# POWER.net
KiCad netlist of a schematic drawn in Altium Designer
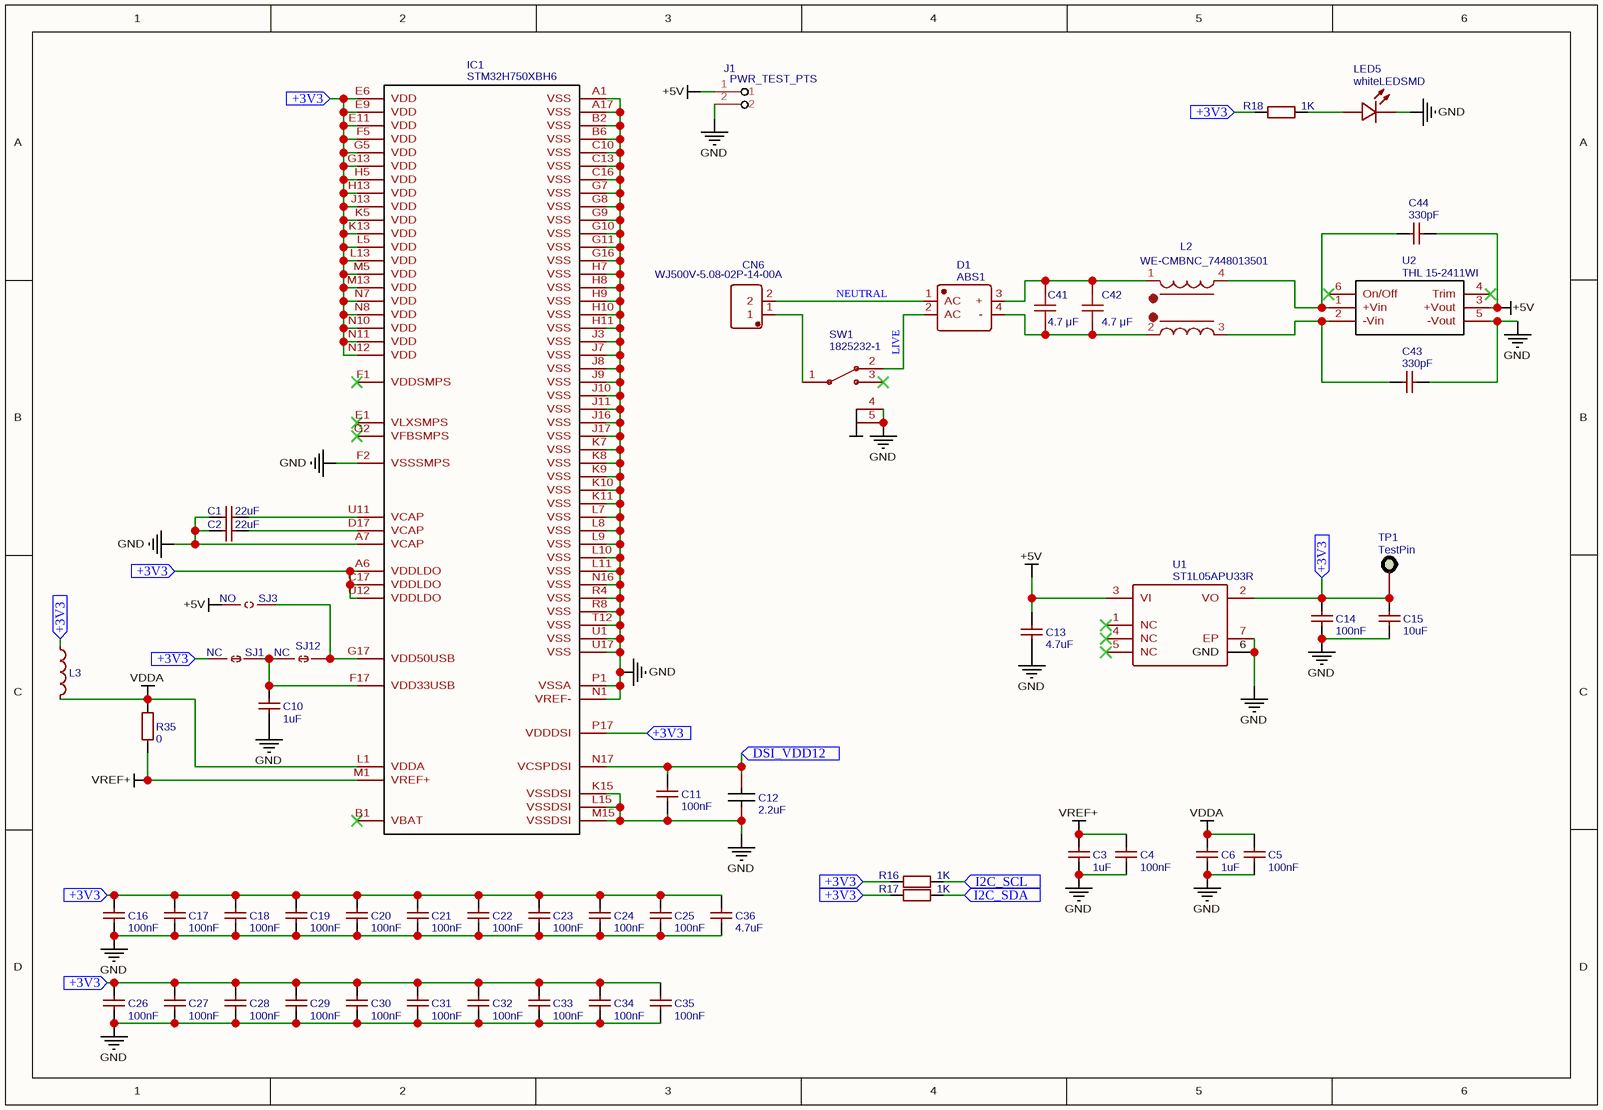
[diagram p0: POWER.schdoc]

(export (version "E")
  (design (tool "Eeschema 10.0.6"))
  (components
    (comp (ref "C1")
      (value "22uF")
      (fields
        (field (name "BOM_MANUFACTURER PART") "CL31A226KPHNNNE")
        (field (name "BOM_SUPPLIER PART") "C5672")
      )
      (libsource (lib "altium-import") (part "root_0_22uF_"))
    )
    (comp (ref "C2")
      (value "22uF")
      (fields
        (field (name "BOM_MANUFACTURER PART") "CL31A226KPHNNNE")
        (field (name "BOM_SUPPLIER PART") "C5672")
      )
      (libsource (lib "altium-import") (part "root_0_22uF_"))
    )
    (comp (ref "C3")
      (value "1uF")
      (fields
        (field (name "BOM_MANUFACTURER PART") "CL10A105KB8NNNC")
        (field (name "BOM_SUPPLIER PART") "C15849")
      )
      (libsource (lib "altium-import") (part "root_1_1uF_"))
    )
    (comp (ref "C4")
      (value "100nF")
      (fields
        (field (name "BOM_MANUFACTURER PART") "CL05B104KO5NNNC")
        (field (name "BOM_SUPPLIER PART") "C1525")
      )
      (libsource (lib "altium-import") (part "root_1_100nF_"))
    )
    (comp (ref "C5")
      (value "100nF")
      (fields
        (field (name "BOM_MANUFACTURER PART") "CL05B104KO5NNNC")
        (field (name "BOM_SUPPLIER PART") "C1525")
      )
      (libsource (lib "altium-import") (part "root_1_100nF_"))
    )
    (comp (ref "C6")
      (value "1uF")
      (fields
        (field (name "BOM_MANUFACTURER PART") "CL10A105KB8NNNC")
        (field (name "BOM_SUPPLIER PART") "C15849")
      )
      (libsource (lib "altium-import") (part "root_1_1uF_"))
    )
    (comp (ref "C10")
      (value "1uF")
      (fields
        (field (name "BOM_MANUFACTURER PART") "CL10A105KB8NNNC")
        (field (name "BOM_SUPPLIER PART") "C15849")
      )
      (libsource (lib "altium-import") (part "root_1_1uF_"))
    )
    (comp (ref "C11")
      (value "100nF")
      (fields
        (field (name "BOM_MANUFACTURER PART") "CL05B104KO5NNNC")
        (field (name "BOM_SUPPLIER PART") "C1525")
      )
      (libsource (lib "altium-import") (part "root_1_100nF_"))
    )
    (comp (ref "C12")
      (value "2.2uF")
      (fields
        (field (name "BOM_MANUFACTURER PART") "CL05A225MQ5NSNC")
        (field (name "BOM_SUPPLIER PART") "C12530")
      )
      (libsource (lib "altium-import") (part "root_1_2.2uF_"))
    )
    (comp (ref "C13")
      (value "4.7uF")
      (fields
        (field (name "BOM_MANUFACTURER PART") "CL05A475MP5NRNC")
        (field (name "BOM_SUPPLIER PART") "C23733")
      )
      (libsource (lib "altium-import") (part "root_1_4.7uF_"))
    )
    (comp (ref "C14")
      (value "100nF")
      (fields
        (field (name "BOM_MANUFACTURER PART") "CL05B104KO5NNNC")
        (field (name "BOM_SUPPLIER PART") "C1525")
      )
      (libsource (lib "altium-import") (part "root_1_100nF_"))
    )
    (comp (ref "C15")
      (value "10uF")
      (fields
        (field (name "BOM_MANUFACTURER PART") "CL21A106KAYNNNE")
        (field (name "BOM_SUPPLIER PART") "C15850")
      )
      (libsource (lib "altium-import") (part "root_1_10uF_"))
    )
    (comp (ref "C16")
      (value "100nF")
      (fields
        (field (name "BOM_MANUFACTURER PART") "CL05B104KO5NNNC")
        (field (name "BOM_SUPPLIER PART") "C1525")
      )
      (libsource (lib "altium-import") (part "root_1_100nF_"))
    )
    (comp (ref "C17")
      (value "100nF")
      (fields
        (field (name "BOM_MANUFACTURER PART") "CL05B104KO5NNNC")
        (field (name "BOM_SUPPLIER PART") "C1525")
      )
      (libsource (lib "altium-import") (part "root_1_100nF_"))
    )
    (comp (ref "C18")
      (value "100nF")
      (fields
        (field (name "BOM_MANUFACTURER PART") "CL05B104KO5NNNC")
        (field (name "BOM_SUPPLIER PART") "C1525")
      )
      (libsource (lib "altium-import") (part "root_1_100nF_"))
    )
    (comp (ref "C19")
      (value "100nF")
      (fields
        (field (name "BOM_MANUFACTURER PART") "CL05B104KO5NNNC")
        (field (name "BOM_SUPPLIER PART") "C1525")
      )
      (libsource (lib "altium-import") (part "root_1_100nF_"))
    )
    (comp (ref "C20")
      (value "100nF")
      (fields
        (field (name "BOM_MANUFACTURER PART") "CL05B104KO5NNNC")
        (field (name "BOM_SUPPLIER PART") "C1525")
      )
      (libsource (lib "altium-import") (part "root_1_100nF_"))
    )
    (comp (ref "C21")
      (value "100nF")
      (fields
        (field (name "BOM_MANUFACTURER PART") "CL05B104KO5NNNC")
        (field (name "BOM_SUPPLIER PART") "C1525")
      )
      (libsource (lib "altium-import") (part "root_1_100nF_"))
    )
    (comp (ref "C22")
      (value "100nF")
      (fields
        (field (name "BOM_MANUFACTURER PART") "CL05B104KO5NNNC")
        (field (name "BOM_SUPPLIER PART") "C1525")
      )
      (libsource (lib "altium-import") (part "root_1_100nF_"))
    )
    (comp (ref "C23")
      (value "100nF")
      (fields
        (field (name "BOM_MANUFACTURER PART") "CL05B104KO5NNNC")
        (field (name "BOM_SUPPLIER PART") "C1525")
      )
      (libsource (lib "altium-import") (part "root_1_100nF_"))
    )
    (comp (ref "C24")
      (value "100nF")
      (fields
        (field (name "BOM_MANUFACTURER PART") "CL05B104KO5NNNC")
        (field (name "BOM_SUPPLIER PART") "C1525")
      )
      (libsource (lib "altium-import") (part "root_1_100nF_"))
    )
    (comp (ref "C25")
      (value "100nF")
      (fields
        (field (name "BOM_MANUFACTURER PART") "CL05B104KO5NNNC")
        (field (name "BOM_SUPPLIER PART") "C1525")
      )
      (libsource (lib "altium-import") (part "root_1_100nF_"))
    )
    (comp (ref "C26")
      (value "100nF")
      (fields
        (field (name "BOM_MANUFACTURER PART") "CL05B104KO5NNNC")
        (field (name "BOM_SUPPLIER PART") "C1525")
      )
      (libsource (lib "altium-import") (part "root_1_100nF_"))
    )
    (comp (ref "C27")
      (value "100nF")
      (fields
        (field (name "BOM_MANUFACTURER PART") "CL05B104KO5NNNC")
        (field (name "BOM_SUPPLIER PART") "C1525")
      )
      (libsource (lib "altium-import") (part "root_1_100nF_"))
    )
    (comp (ref "C28")
      (value "100nF")
      (fields
        (field (name "BOM_MANUFACTURER PART") "CL05B104KO5NNNC")
        (field (name "BOM_SUPPLIER PART") "C1525")
      )
      (libsource (lib "altium-import") (part "root_1_100nF_"))
    )
    (comp (ref "C29")
      (value "100nF")
      (fields
        (field (name "BOM_MANUFACTURER PART") "CL05B104KO5NNNC")
        (field (name "BOM_SUPPLIER PART") "C1525")
      )
      (libsource (lib "altium-import") (part "root_1_100nF_"))
    )
    (comp (ref "C30")
      (value "100nF")
      (fields
        (field (name "BOM_MANUFACTURER PART") "CL05B104KO5NNNC")
        (field (name "BOM_SUPPLIER PART") "C1525")
      )
      (libsource (lib "altium-import") (part "root_1_100nF_"))
    )
    (comp (ref "C31")
      (value "100nF")
      (fields
        (field (name "BOM_MANUFACTURER PART") "CL05B104KO5NNNC")
        (field (name "BOM_SUPPLIER PART") "C1525")
      )
      (libsource (lib "altium-import") (part "root_1_100nF_"))
    )
    (comp (ref "C32")
      (value "100nF")
      (fields
        (field (name "BOM_MANUFACTURER PART") "CL05B104KO5NNNC")
        (field (name "BOM_SUPPLIER PART") "C1525")
      )
      (libsource (lib "altium-import") (part "root_1_100nF_"))
    )
    (comp (ref "C33")
      (value "100nF")
      (fields
        (field (name "BOM_MANUFACTURER PART") "CL05B104KO5NNNC")
        (field (name "BOM_SUPPLIER PART") "C1525")
      )
      (libsource (lib "altium-import") (part "root_1_100nF_"))
    )
    (comp (ref "C34")
      (value "100nF")
      (fields
        (field (name "BOM_MANUFACTURER PART") "CL05B104KO5NNNC")
        (field (name "BOM_SUPPLIER PART") "C1525")
      )
      (libsource (lib "altium-import") (part "root_1_100nF_"))
    )
    (comp (ref "C35")
      (value "100nF")
      (fields
        (field (name "BOM_MANUFACTURER PART") "CL05B104KO5NNNC")
        (field (name "BOM_SUPPLIER PART") "C1525")
      )
      (libsource (lib "altium-import") (part "root_1_100nF_"))
    )
    (comp (ref "C36")
      (value "4.7uF")
      (fields
        (field (name "BOM_MANUFACTURER PART") "CL05A475MP5NRNC")
        (field (name "BOM_SUPPLIER PART") "C23733")
      )
      (libsource (lib "altium-import") (part "root_1_4.7uF_"))
    )
    (comp (ref "C41")
      (value "4.7 μF")
      (fields (field (name "BOM_SUPPLIER PART") "C16036") (field (name "CONTRIBUTOR") "LCSC"))
      (libsource (lib "altium-import") (part "root_0_4.7 μF_"))
    )
    (comp (ref "C42")
      (value "4.7 μF")
      (fields (field (name "BOM_SUPPLIER PART") "C16036") (field (name "CONTRIBUTOR") "LCSC"))
      (libsource (lib "altium-import") (part "root_0_4.7 μF_"))
    )
    (comp (ref "C43")
      (value "330pF")
      (fields
        (field (name "BOM_MANUFACTURER PART") "1206B331K501NT")
        (field (name "BOM_SUPPLIER PART") "C46377")
      )
      (libsource (lib "altium-import") (part "root_0_330pF_"))
    )
    (comp (ref "C44")
      (value "330pF")
      (fields
        (field (name "BOM_MANUFACTURER PART") "1206B331K501NT")
        (field (name "BOM_SUPPLIER PART") "C46377")
      )
      (libsource (lib "altium-import") (part "root_0_330pF_"))
    )
    (comp (ref "CN6")
      (value "WJ500V-5.08-02P-14-00A")
      (fields (field (name "BOM_SUPPLIER PART") "C138464") (field (name "CONTRIBUTOR") "LCSC"))
      (libsource (lib "altium-import") (part "root_2_WJ500V-5.08-02P-14-00A_"))
    )
    (comp (ref "D1")
      (value "ABS1")
      (fields (field (name "BOM_SUPPLIER PART") "C130890") (field (name "CONTRIBUTOR") "LCSC"))
      (libsource (lib "altium-import") (part "root_0_ABS1_"))
    )
    (comp (ref "IC1")
      (value "STM32H750XBH6")
      (fields (field (name "SUBPART_NO") "1") (field (name "CONTRIBUTOR") "Ke'Ondrae_Mell"))
      (libsource (lib "altium-import") (part "root_0_STM32H750XBH6_"))
    )
    (comp (ref "J1")
      (value "PWR_TEST_PTS")
      (fields (field (name "CONTRIBUTOR") "Claudio Quartarone"))
      (libsource (lib "altium-import") (part "root_3_PWR_TEST_PTS_"))
    )
    (comp (ref "L2")
      (value "WE-CMBNC_7448013501")
      (description "WE-CMBNC Common Mode Power Line Choke Nanocrystalline")
      (libsource (lib "altium-import") (part "root_0_WE-CMBNC_7448013501_"))
    )
    (comp (ref "L3")
      (value "FCM1608KF-601T03")
      (fields (field (name "BOM_SUPPLIER PART") "C141723") (field (name "CONTRIBUTOR") "LCSC"))
      (libsource (lib "altium-import") (part "root_3_FCM1608KF-601T03_"))
    )
    (comp (ref "LED5")
      (value "whiteLEDSMD")
      (fields (field (name "BOM_SUPPLIER PART") "C34499"))
      (libsource (lib "altium-import") (part "root_0_whiteLEDSMD_"))
    )
    (comp (ref "R16")
      (value "1K")
      (fields
        (field (name "BOM_MANUFACTURER PART") "0402WGF1001TCE")
        (field (name "BOM_SUPPLIER PART") "C11702")
      )
      (libsource (lib "altium-import") (part "root_0_1K_"))
    )
    (comp (ref "R17")
      (value "1K")
      (fields
        (field (name "BOM_MANUFACTURER PART") "0402WGF1001TCE")
        (field (name "BOM_SUPPLIER PART") "C11702")
      )
      (libsource (lib "altium-import") (part "root_0_1K_"))
    )
    (comp (ref "R18")
      (value "1K")
      (fields
        (field (name "BOM_MANUFACTURER PART") "0402WGF1001TCE")
        (field (name "BOM_SUPPLIER PART") "C11702")
      )
      (libsource (lib "altium-import") (part "root_0_1K_"))
    )
    (comp (ref "R35")
      (value "0")
      (fields
        (field (name "BOM_MANUFACTURER PART") "RK73Z1ETTP")
        (field (name "BOM_SUPPLIER PART") "C131359")
      )
      (libsource (lib "altium-import") (part "root_1_0_"))
    )
    (comp (ref "SJ1")
      (value "NC")
      (fields (field (name "CONTRIBUTOR") "SparkFun"))
      (libsource (lib "altium-import") (part "root_0_NC_"))
    )
    (comp (ref "SJ3")
      (value "NO")
      (fields (field (name "CONTRIBUTOR") "SparkFun"))
      (libsource (lib "altium-import") (part "root_0_NO_"))
    )
    (comp (ref "SJ12")
      (value "NC")
      (fields (field (name "CONTRIBUTOR") "SparkFun"))
      (libsource (lib "altium-import") (part "root_0_NC_"))
    )
    (comp (ref "SW1")
      (value "1825232-1")
      (fields (field (name "BOM_SUPPLIER PART") "655-1825232-1") (field (name "CONTRIBUTOR") "nathantct"))
      (libsource (lib "altium-import") (part "root_0_1825232-1_"))
    )
    (comp (ref "TP1")
      (value "TestPin")
      (fields (field (name "CONTRIBUTOR") "alan.green"))
      (libsource (lib "altium-import") (part "root_0_TestPin_"))
    )
    (comp (ref "U1")
      (value "ST1L05APU33R")
      (description "Very Low Quiescent BiCMOS Voltage Regulator, 3.3V, 6-Pin VFDFPN, Tape and Reel")
      (libsource (lib "altium-import") (part "root_0_ST1L05APU33R_"))
    )
    (comp (ref "U2")
      (value "THL 15-2411WI")
      (fields
        (field (name "BOM_SUPPLIER PART") "1951-3321-ND")
        (field (name "CONTRIBUTOR") "louis.grueninger")
      )
      (libsource (lib "altium-import") (part "root_0_THL 15-2411WI_"))
    )
  )
  (nets
    (net (code "1") (name "+5V") (class "Default")
      (node (ref "C13") (pin "2") (pinfunction "2_2") (pintype "passive"))
      (node (ref "C44") (pin "2") (pinfunction "2_2") (pintype "passive"))
      (node (ref "J1") (pin "1") (pinfunction "1_1") (pintype "passive"))
      (node (ref "SJ3") (pin "1") (pinfunction "1_1") (pintype "passive"))
      (node (ref "U1") (pin "3") (pinfunction "VI_3") (pintype "passive"))
      (node (ref "U2") (pin "3") (pinfunction "+Vout_3") (pintype "passive"))
    )
    (net (code "2") (name "/+3V3") (class "Default")
      (node (ref "C14") (pin "2") (pinfunction "2_2") (pintype "passive"))
      (node (ref "C15") (pin "2") (pinfunction "2_2") (pintype "passive"))
      (node (ref "C16") (pin "2") (pinfunction "2_2") (pintype "passive"))
      (node (ref "C17") (pin "2") (pinfunction "2_2") (pintype "passive"))
      (node (ref "C18") (pin "2") (pinfunction "2_2") (pintype "passive"))
      (node (ref "C19") (pin "2") (pinfunction "2_2") (pintype "passive"))
      (node (ref "C20") (pin "2") (pinfunction "2_2") (pintype "passive"))
      (node (ref "C21") (pin "2") (pinfunction "2_2") (pintype "passive"))
      (node (ref "C22") (pin "2") (pinfunction "2_2") (pintype "passive"))
      (node (ref "C23") (pin "2") (pinfunction "2_2") (pintype "passive"))
      (node (ref "C24") (pin "2") (pinfunction "2_2") (pintype "passive"))
      (node (ref "C25") (pin "2") (pinfunction "2_2") (pintype "passive"))
      (node (ref "C26") (pin "2") (pinfunction "2_2") (pintype "passive"))
      (node (ref "C27") (pin "2") (pinfunction "2_2") (pintype "passive"))
      (node (ref "C28") (pin "2") (pinfunction "2_2") (pintype "passive"))
      (node (ref "C29") (pin "2") (pinfunction "2_2") (pintype "passive"))
      (node (ref "C30") (pin "2") (pinfunction "2_2") (pintype "passive"))
      (node (ref "C31") (pin "2") (pinfunction "2_2") (pintype "passive"))
      (node (ref "C32") (pin "2") (pinfunction "2_2") (pintype "passive"))
      (node (ref "C33") (pin "2") (pinfunction "2_2") (pintype "passive"))
      (node (ref "C34") (pin "2") (pinfunction "2_2") (pintype "passive"))
      (node (ref "C35") (pin "2") (pinfunction "2_2") (pintype "passive"))
      (node (ref "C36") (pin "2") (pinfunction "2_2") (pintype "passive"))
      (node (ref "IC1") (pin "A6") (pinfunction "VDDLDO_A6") (pintype "passive"))
      (node (ref "IC1") (pin "C17") (pinfunction "VDDLDO_C17") (pintype "passive"))
      (node (ref "IC1") (pin "E11") (pinfunction "VDD_E11") (pintype "passive"))
      (node (ref "IC1") (pin "E6") (pinfunction "VDD_E6") (pintype "passive"))
      (node (ref "IC1") (pin "E9") (pinfunction "VDD_E9") (pintype "passive"))
      (node (ref "IC1") (pin "F5") (pinfunction "VDD_F5") (pintype "passive"))
      (node (ref "IC1") (pin "G13") (pinfunction "VDD_G13") (pintype "passive"))
      (node (ref "IC1") (pin "G5") (pinfunction "VDD_G5") (pintype "passive"))
      (node (ref "IC1") (pin "H13") (pinfunction "VDD_H13") (pintype "passive"))
      (node (ref "IC1") (pin "H5") (pinfunction "VDD_H5") (pintype "passive"))
      (node (ref "IC1") (pin "J13") (pinfunction "VDD_J13") (pintype "passive"))
      (node (ref "IC1") (pin "K13") (pinfunction "VDD_K13") (pintype "passive"))
      (node (ref "IC1") (pin "K5") (pinfunction "VDD_K5") (pintype "passive"))
      (node (ref "IC1") (pin "L13") (pinfunction "VDD_L13") (pintype "passive"))
      (node (ref "IC1") (pin "L5") (pinfunction "VDD_L5") (pintype "passive"))
      (node (ref "IC1") (pin "M13") (pinfunction "VDD_M13") (pintype "passive"))
      (node (ref "IC1") (pin "M5") (pinfunction "VDD_M5") (pintype "passive"))
      (node (ref "IC1") (pin "N10") (pinfunction "VDD_N10") (pintype "passive"))
      (node (ref "IC1") (pin "N11") (pinfunction "VDD_N11") (pintype "passive"))
      (node (ref "IC1") (pin "N12") (pinfunction "VDD_N12") (pintype "passive"))
      (node (ref "IC1") (pin "N7") (pinfunction "VDD_N7") (pintype "passive"))
      (node (ref "IC1") (pin "N8") (pinfunction "VDD_N8") (pintype "passive"))
      (node (ref "IC1") (pin "P17") (pinfunction "VDDDSI_P17") (pintype "passive"))
      (node (ref "IC1") (pin "U12") (pinfunction "VDDLDO_U12") (pintype "passive"))
      (node (ref "L3") (pin "1") (pinfunction "1_1") (pintype "passive"))
      (node (ref "R16") (pin "1") (pinfunction "1_1") (pintype "passive"))
      (node (ref "R17") (pin "1") (pinfunction "1_1") (pintype "passive"))
      (node (ref "R18") (pin "1") (pinfunction "1_1") (pintype "passive"))
      (node (ref "SJ1") (pin "1") (pinfunction "1_1") (pintype "passive"))
      (node (ref "TP1") (pin "1") (pinfunction "1_1") (pintype "passive"))
      (node (ref "U1") (pin "2") (pinfunction "VO_2") (pintype "passive"))
    )
    (net (code "3") (name "/DSI_VDD12") (class "Default")
      (node (ref "C11") (pin "2") (pinfunction "2_2") (pintype "passive"))
      (node (ref "C12") (pin "2") (pinfunction "2_2") (pintype "passive"))
      (node (ref "IC1") (pin "N17") (pinfunction "VCSPDSI_N17") (pintype "passive"))
    )
    (net (code "4") (name "/I2C_SCL") (class "Default")
      (node (ref "R16") (pin "2") (pinfunction "2_2") (pintype "passive"))
    )
    (net (code "5") (name "/I2C_SDA") (class "Default")
      (node (ref "R17") (pin "2") (pinfunction "2_2") (pintype "passive"))
    )
    (net (code "6") (name "/LIVE") (class "Default")
      (node (ref "D1") (pin "2") (pinfunction "AC_2") (pintype "passive"))
      (node (ref "SW1") (pin "2") (pinfunction "2_2") (pintype "passive"))
    )
    (net (code "7") (name "/NEUTRAL") (class "Default")
      (node (ref "CN6") (pin "2") (pinfunction "2_2") (pintype "passive"))
      (node (ref "D1") (pin "1") (pinfunction "AC_1") (pintype "passive"))
    )
    (net (code "8") (name "GND") (class "Default")
      (node (ref "C1") (pin "1") (pinfunction "1_1") (pintype "passive"))
      (node (ref "C10") (pin "1") (pinfunction "1_1") (pintype "passive"))
      (node (ref "C11") (pin "1") (pinfunction "1_1") (pintype "passive"))
      (node (ref "C12") (pin "1") (pinfunction "1_1") (pintype "passive"))
      (node (ref "C13") (pin "1") (pinfunction "1_1") (pintype "passive"))
      (node (ref "C14") (pin "1") (pinfunction "1_1") (pintype "passive"))
      (node (ref "C15") (pin "1") (pinfunction "1_1") (pintype "passive"))
      (node (ref "C16") (pin "1") (pinfunction "1_1") (pintype "passive"))
      (node (ref "C17") (pin "1") (pinfunction "1_1") (pintype "passive"))
      (node (ref "C18") (pin "1") (pinfunction "1_1") (pintype "passive"))
      (node (ref "C19") (pin "1") (pinfunction "1_1") (pintype "passive"))
      (node (ref "C2") (pin "1") (pinfunction "1_1") (pintype "passive"))
      (node (ref "C20") (pin "1") (pinfunction "1_1") (pintype "passive"))
      (node (ref "C21") (pin "1") (pinfunction "1_1") (pintype "passive"))
      (node (ref "C22") (pin "1") (pinfunction "1_1") (pintype "passive"))
      (node (ref "C23") (pin "1") (pinfunction "1_1") (pintype "passive"))
      (node (ref "C24") (pin "1") (pinfunction "1_1") (pintype "passive"))
      (node (ref "C25") (pin "1") (pinfunction "1_1") (pintype "passive"))
      (node (ref "C26") (pin "1") (pinfunction "1_1") (pintype "passive"))
      (node (ref "C27") (pin "1") (pinfunction "1_1") (pintype "passive"))
      (node (ref "C28") (pin "1") (pinfunction "1_1") (pintype "passive"))
      (node (ref "C29") (pin "1") (pinfunction "1_1") (pintype "passive"))
      (node (ref "C3") (pin "1") (pinfunction "1_1") (pintype "passive"))
      (node (ref "C30") (pin "1") (pinfunction "1_1") (pintype "passive"))
      (node (ref "C31") (pin "1") (pinfunction "1_1") (pintype "passive"))
      (node (ref "C32") (pin "1") (pinfunction "1_1") (pintype "passive"))
      (node (ref "C33") (pin "1") (pinfunction "1_1") (pintype "passive"))
      (node (ref "C34") (pin "1") (pinfunction "1_1") (pintype "passive"))
      (node (ref "C35") (pin "1") (pinfunction "1_1") (pintype "passive"))
      (node (ref "C36") (pin "1") (pinfunction "1_1") (pintype "passive"))
      (node (ref "C4") (pin "1") (pinfunction "1_1") (pintype "passive"))
      (node (ref "C43") (pin "2") (pinfunction "2_2") (pintype "passive"))
      (node (ref "C5") (pin "1") (pinfunction "1_1") (pintype "passive"))
      (node (ref "C6") (pin "1") (pinfunction "1_1") (pintype "passive"))
      (node (ref "IC1") (pin "A1") (pinfunction "VSS_A1") (pintype "passive"))
      (node (ref "IC1") (pin "A17") (pinfunction "VSS_A17") (pintype "passive"))
      (node (ref "IC1") (pin "A7") (pinfunction "VCAP_A7") (pintype "passive"))
      (node (ref "IC1") (pin "B2") (pinfunction "VSS_B2") (pintype "passive"))
      (node (ref "IC1") (pin "B6") (pinfunction "VSS_B6") (pintype "passive"))
      (node (ref "IC1") (pin "C10") (pinfunction "VSS_C10") (pintype "passive"))
      (node (ref "IC1") (pin "C13") (pinfunction "VSS_C13") (pintype "passive"))
      (node (ref "IC1") (pin "C16") (pinfunction "VSS_C16") (pintype "passive"))
      (node (ref "IC1") (pin "F2") (pinfunction "VSSSMPS_F2") (pintype "passive"))
      (node (ref "IC1") (pin "G10") (pinfunction "VSS_G10") (pintype "passive"))
      (node (ref "IC1") (pin "G11") (pinfunction "VSS_G11") (pintype "passive"))
      (node (ref "IC1") (pin "G16") (pinfunction "VSS_G16") (pintype "passive"))
      (node (ref "IC1") (pin "G7") (pinfunction "VSS_G7") (pintype "passive"))
      (node (ref "IC1") (pin "G8") (pinfunction "VSS_G8") (pintype "passive"))
      (node (ref "IC1") (pin "G9") (pinfunction "VSS_G9") (pintype "passive"))
      (node (ref "IC1") (pin "H10") (pinfunction "VSS_H10") (pintype "passive"))
      (node (ref "IC1") (pin "H11") (pinfunction "VSS_H11") (pintype "passive"))
      (node (ref "IC1") (pin "H7") (pinfunction "VSS_H7") (pintype "passive"))
      (node (ref "IC1") (pin "H8") (pinfunction "VSS_H8") (pintype "passive"))
      (node (ref "IC1") (pin "H9") (pinfunction "VSS_H9") (pintype "passive"))
      (node (ref "IC1") (pin "J10") (pinfunction "VSS_J10") (pintype "passive"))
      (node (ref "IC1") (pin "J11") (pinfunction "VSS_J11") (pintype "passive"))
      (node (ref "IC1") (pin "J16") (pinfunction "VSS_J16") (pintype "passive"))
      (node (ref "IC1") (pin "J17") (pinfunction "VSS_J17") (pintype "passive"))
      (node (ref "IC1") (pin "J3") (pinfunction "VSS_J3") (pintype "passive"))
      (node (ref "IC1") (pin "J7") (pinfunction "VSS_J7") (pintype "passive"))
      (node (ref "IC1") (pin "J8") (pinfunction "VSS_J8") (pintype "passive"))
      (node (ref "IC1") (pin "J9") (pinfunction "VSS_J9") (pintype "passive"))
      (node (ref "IC1") (pin "K10") (pinfunction "VSS_K10") (pintype "passive"))
      (node (ref "IC1") (pin "K11") (pinfunction "VSS_K11") (pintype "passive"))
      (node (ref "IC1") (pin "K15") (pinfunction "VSSDSI_K15") (pintype "passive"))
      (node (ref "IC1") (pin "K7") (pinfunction "VSS_K7") (pintype "passive"))
      (node (ref "IC1") (pin "K8") (pinfunction "VSS_K8") (pintype "passive"))
      (node (ref "IC1") (pin "K9") (pinfunction "VSS_K9") (pintype "passive"))
      (node (ref "IC1") (pin "L10") (pinfunction "VSS_L10") (pintype "passive"))
      (node (ref "IC1") (pin "L11") (pinfunction "VSS_L11") (pintype "passive"))
      (node (ref "IC1") (pin "L15") (pinfunction "VSSDSI_L15") (pintype "passive"))
      (node (ref "IC1") (pin "L7") (pinfunction "VSS_L7") (pintype "passive"))
      (node (ref "IC1") (pin "L8") (pinfunction "VSS_L8") (pintype "passive"))
      (node (ref "IC1") (pin "L9") (pinfunction "VSS_L9") (pintype "passive"))
      (node (ref "IC1") (pin "M15") (pinfunction "VSSDSI_M15") (pintype "passive"))
      (node (ref "IC1") (pin "N1") (pinfunction "VREF-_N1") (pintype "passive"))
      (node (ref "IC1") (pin "N16") (pinfunction "VSS_N16") (pintype "passive"))
      (node (ref "IC1") (pin "P1") (pinfunction "VSSA_P1") (pintype "passive"))
      (node (ref "IC1") (pin "R4") (pinfunction "VSS_R4") (pintype "passive"))
      (node (ref "IC1") (pin "R8") (pinfunction "VSS_R8") (pintype "passive"))
      (node (ref "IC1") (pin "T12") (pinfunction "VSS_T12") (pintype "passive"))
      (node (ref "IC1") (pin "U1") (pinfunction "VSS_U1") (pintype "passive"))
      (node (ref "IC1") (pin "U17") (pinfunction "VSS_U17") (pintype "passive"))
      (node (ref "J1") (pin "2") (pinfunction "2_2") (pintype "passive"))
      (node (ref "LED5") (pin "2") (pinfunction "K_2") (pintype "passive"))
      (node (ref "SW1") (pin "4") (pinfunction "4_4") (pintype "passive"))
      (node (ref "SW1") (pin "5") (pinfunction "5_5") (pintype "passive"))
      (node (ref "U1") (pin "6") (pinfunction "GND_6") (pintype "passive"))
      (node (ref "U1") (pin "7") (pinfunction "EP_7") (pintype "passive"))
      (node (ref "U2") (pin "5") (pinfunction "-Vout_5") (pintype "passive"))
    )
    (net (code "9") (name "Net-(C1-Pad2)") (class "Default")
      (node (ref "C1") (pin "2") (pinfunction "2_2") (pintype "passive"))
      (node (ref "IC1") (pin "U11") (pinfunction "VCAP_U11") (pintype "passive"))
    )
    (net (code "10") (name "Net-(C2-Pad2)") (class "Default")
      (node (ref "C2") (pin "2") (pinfunction "2_2") (pintype "passive"))
      (node (ref "IC1") (pin "D17") (pinfunction "VCAP_D17") (pintype "passive"))
    )
    (net (code "11") (name "Net-(CN6-Pad1)") (class "Default")
      (node (ref "CN6") (pin "1") (pinfunction "1_1") (pintype "passive"))
      (node (ref "SW1") (pin "1") (pinfunction "1_1") (pintype "passive"))
    )
    (net (code "12") (name "Net-(D1-+)") (class "Default")
      (node (ref "C41") (pin "2") (pinfunction "2_2") (pintype "passive"))
      (node (ref "C42") (pin "2") (pinfunction "2_2") (pintype "passive"))
      (node (ref "D1") (pin "3") (pinfunction "+_3") (pintype "passive"))
      (node (ref "L2") (pin "1") (pinfunction "1_1") (pintype "passive"))
    )
    (net (code "13") (name "Net-(D1--)") (class "Default")
      (node (ref "C41") (pin "1") (pinfunction "1_1") (pintype "passive"))
      (node (ref "C42") (pin "1") (pinfunction "1_1") (pintype "passive"))
      (node (ref "D1") (pin "4") (pinfunction "-_4") (pintype "passive"))
      (node (ref "L2") (pin "2") (pinfunction "4_2") (pintype "passive"))
    )
    (net (code "14") (name "Net-(IC1-VDD33USB)") (class "Default")
      (node (ref "C10") (pin "2") (pinfunction "2_2") (pintype "passive"))
      (node (ref "IC1") (pin "F17") (pinfunction "VDD33USB_F17") (pintype "passive"))
      (node (ref "SJ1") (pin "2") (pinfunction "2_2") (pintype "passive"))
      (node (ref "SJ12") (pin "1") (pinfunction "1_1") (pintype "passive"))
    )
    (net (code "15") (name "Net-(IC1-VDD50USB)") (class "Default")
      (node (ref "IC1") (pin "G17") (pinfunction "VDD50USB_G17") (pintype "passive"))
      (node (ref "SJ12") (pin "2") (pinfunction "2_2") (pintype "passive"))
      (node (ref "SJ3") (pin "2") (pinfunction "2_2") (pintype "passive"))
    )
    (net (code "16") (name "Net-(L2-2)") (class "Default")
      (node (ref "C44") (pin "1") (pinfunction "1_1") (pintype "passive"))
      (node (ref "L2") (pin "4") (pinfunction "2_4") (pintype "passive"))
      (node (ref "U2") (pin "1") (pinfunction "+Vin_1") (pintype "passive"))
    )
    (net (code "17") (name "Net-(LED5-A)") (class "Default")
      (node (ref "LED5") (pin "1") (pinfunction "A_1") (pintype "passive"))
      (node (ref "R18") (pin "2") (pinfunction "2_2") (pintype "passive"))
    )
    (net (code "18") (name "Net-(U2--Vin)") (class "Default")
      (node (ref "C43") (pin "1") (pinfunction "1_1") (pintype "passive"))
      (node (ref "L2") (pin "3") (pinfunction "3_3") (pintype "passive"))
      (node (ref "U2") (pin "2") (pinfunction "-Vin_2") (pintype "passive"))
    )
    (net (code "19") (name "VDDA") (class "Default")
      (node (ref "C5") (pin "2") (pinfunction "2_2") (pintype "passive"))
      (node (ref "C6") (pin "2") (pinfunction "2_2") (pintype "passive"))
      (node (ref "IC1") (pin "L1") (pinfunction "VDDA_L1") (pintype "passive"))
      (node (ref "L3") (pin "2") (pinfunction "2_2") (pintype "passive"))
      (node (ref "R35") (pin "2") (pinfunction "2_2") (pintype "passive"))
    )
    (net (code "20") (name "VREF+") (class "Default")
      (node (ref "C3") (pin "2") (pinfunction "2_2") (pintype "passive"))
      (node (ref "C4") (pin "2") (pinfunction "2_2") (pintype "passive"))
      (node (ref "IC1") (pin "M1") (pinfunction "VREF+_M1") (pintype "passive"))
      (node (ref "R35") (pin "1") (pinfunction "1_1") (pintype "passive"))
    )
    (net (code "21") (name "unconnected-(IC1-VBAT-PadB1)") (class "Default")
      (node (ref "IC1") (pin "B1") (pinfunction "VBAT_B1") (pintype "passive+no_connect"))
    )
    (net (code "22") (name "unconnected-(IC1-VDDSMPS-PadF1)") (class "Default")
      (node (ref "IC1") (pin "F1") (pinfunction "VDDSMPS_F1") (pintype "passive+no_connect"))
    )
    (net (code "23") (name "unconnected-(IC1-VFBSMPS-PadG2)") (class "Default")
      (node (ref "IC1") (pin "G2") (pinfunction "VFBSMPS_G2") (pintype "passive+no_connect"))
    )
    (net (code "24") (name "unconnected-(IC1-VLXSMPS-PadE1)") (class "Default")
      (node (ref "IC1") (pin "E1") (pinfunction "VLXSMPS_E1") (pintype "passive+no_connect"))
    )
    (net (code "25") (name "unconnected-(SW1-Pad3)") (class "Default")
      (node (ref "SW1") (pin "3") (pinfunction "3_3") (pintype "passive+no_connect"))
    )
    (net (code "26") (name "unconnected-(U1-NC-Pad1)") (class "Default")
      (node (ref "U1") (pin "1") (pinfunction "NC_1") (pintype "passive+no_connect"))
    )
    (net (code "27") (name "unconnected-(U1-NC-Pad4)") (class "Default")
      (node (ref "U1") (pin "4") (pinfunction "NC_4") (pintype "passive+no_connect"))
    )
    (net (code "28") (name "unconnected-(U1-NC-Pad5)") (class "Default")
      (node (ref "U1") (pin "5") (pinfunction "NC_5") (pintype "passive+no_connect"))
    )
    (net (code "29") (name "unconnected-(U2-On{slash}Off-Pad6)") (class "Default")
      (node (ref "U2") (pin "6") (pinfunction "On/Off_6") (pintype "passive+no_connect"))
    )
    (net (code "30") (name "unconnected-(U2-Trim-Pad4)") (class "Default")
      (node (ref "U2") (pin "4") (pinfunction "Trim_4") (pintype "passive+no_connect"))
    )
  )
)
